# controller11_2.net
KiCad netlist of a schematic drawn in EAGLE
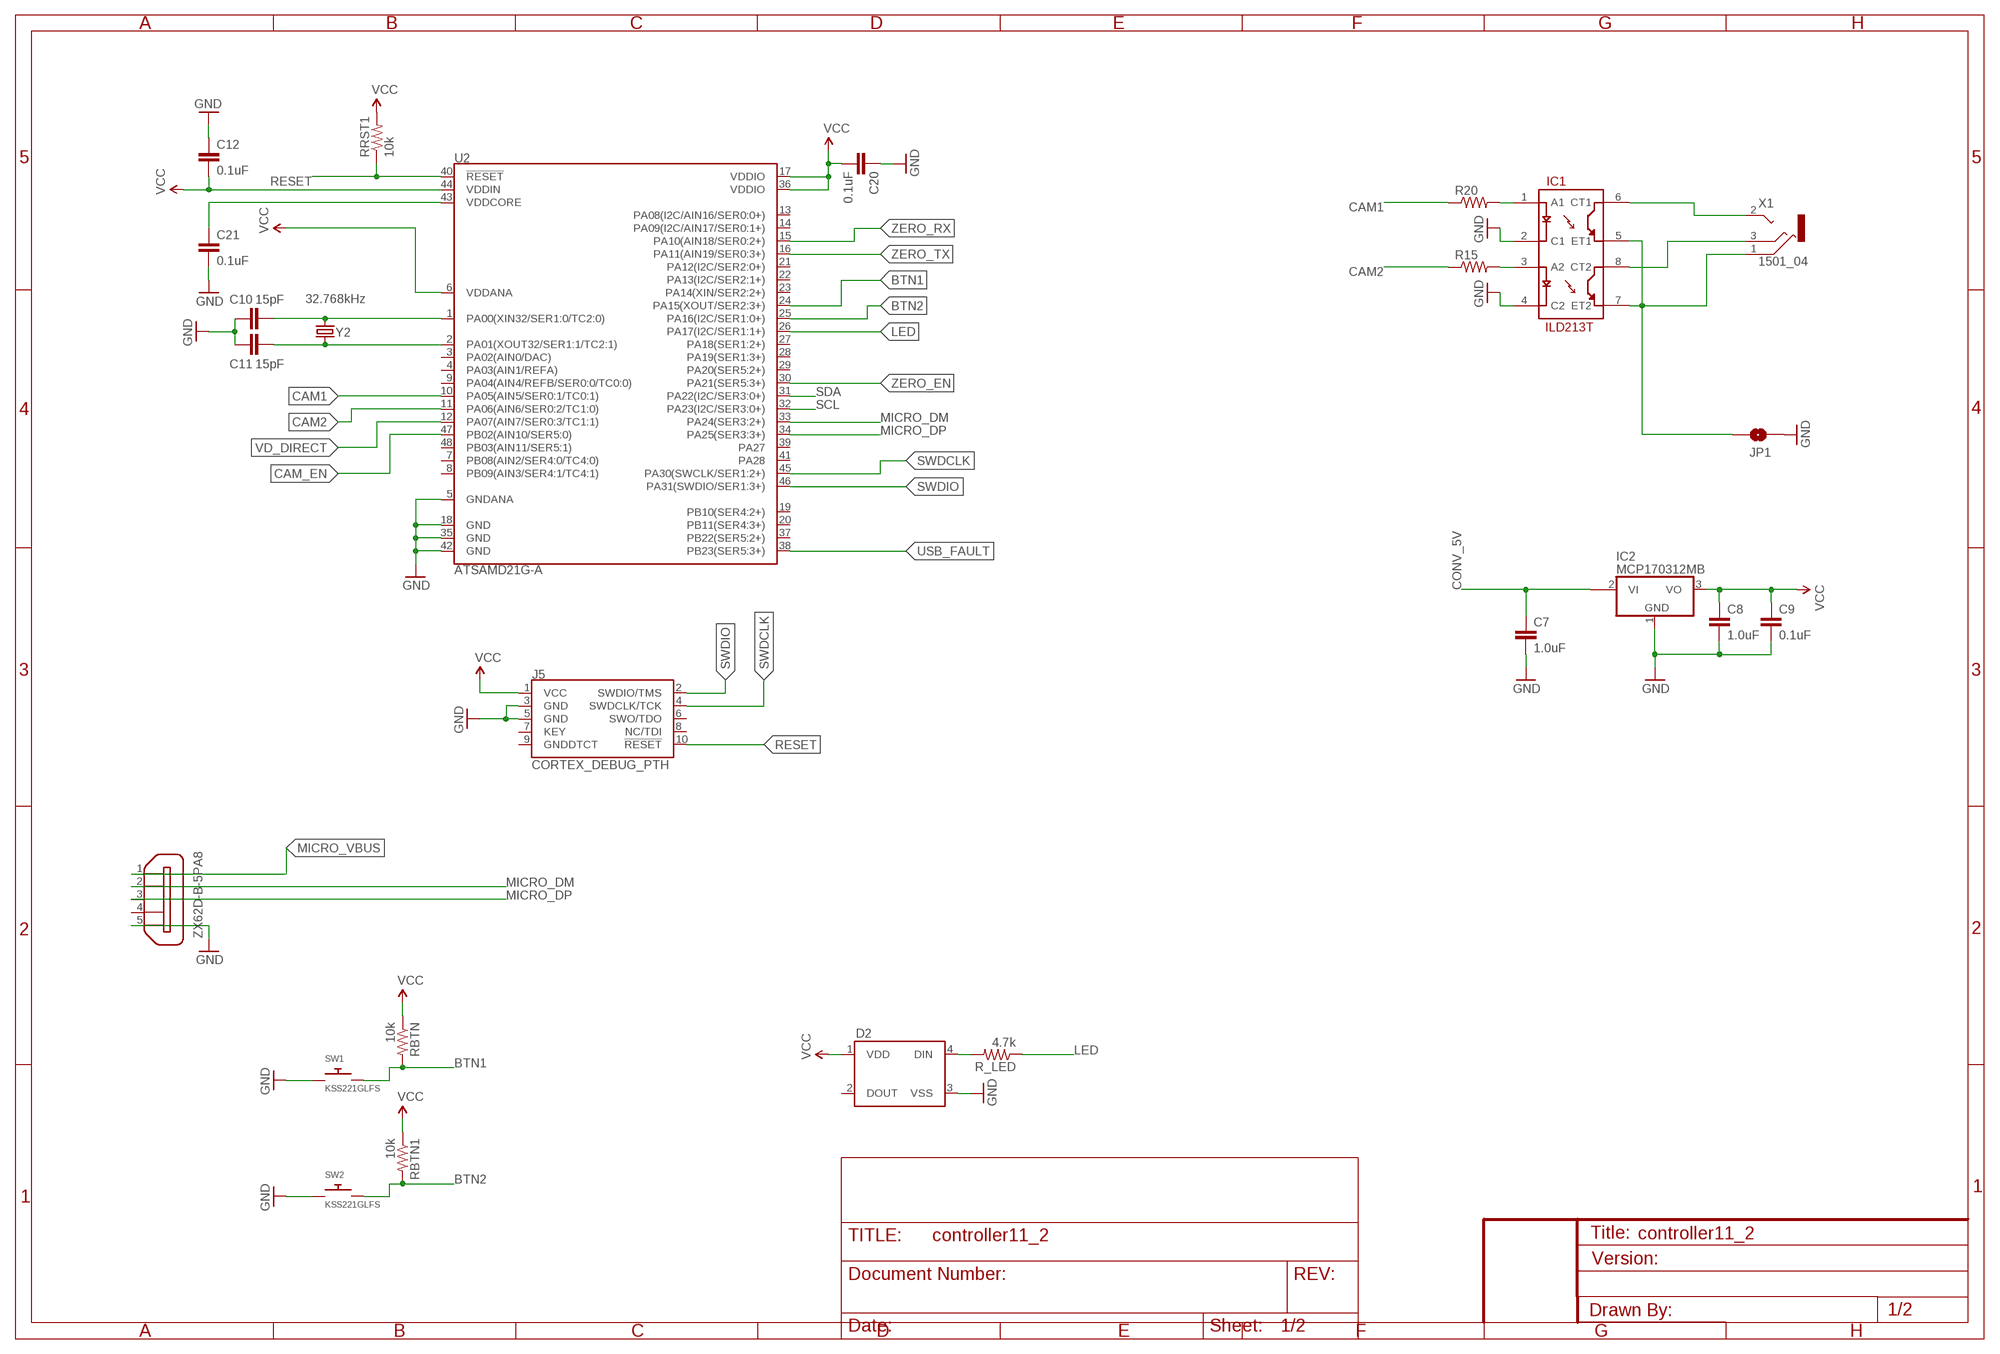
[diagram p0: schematic, sheet 1]
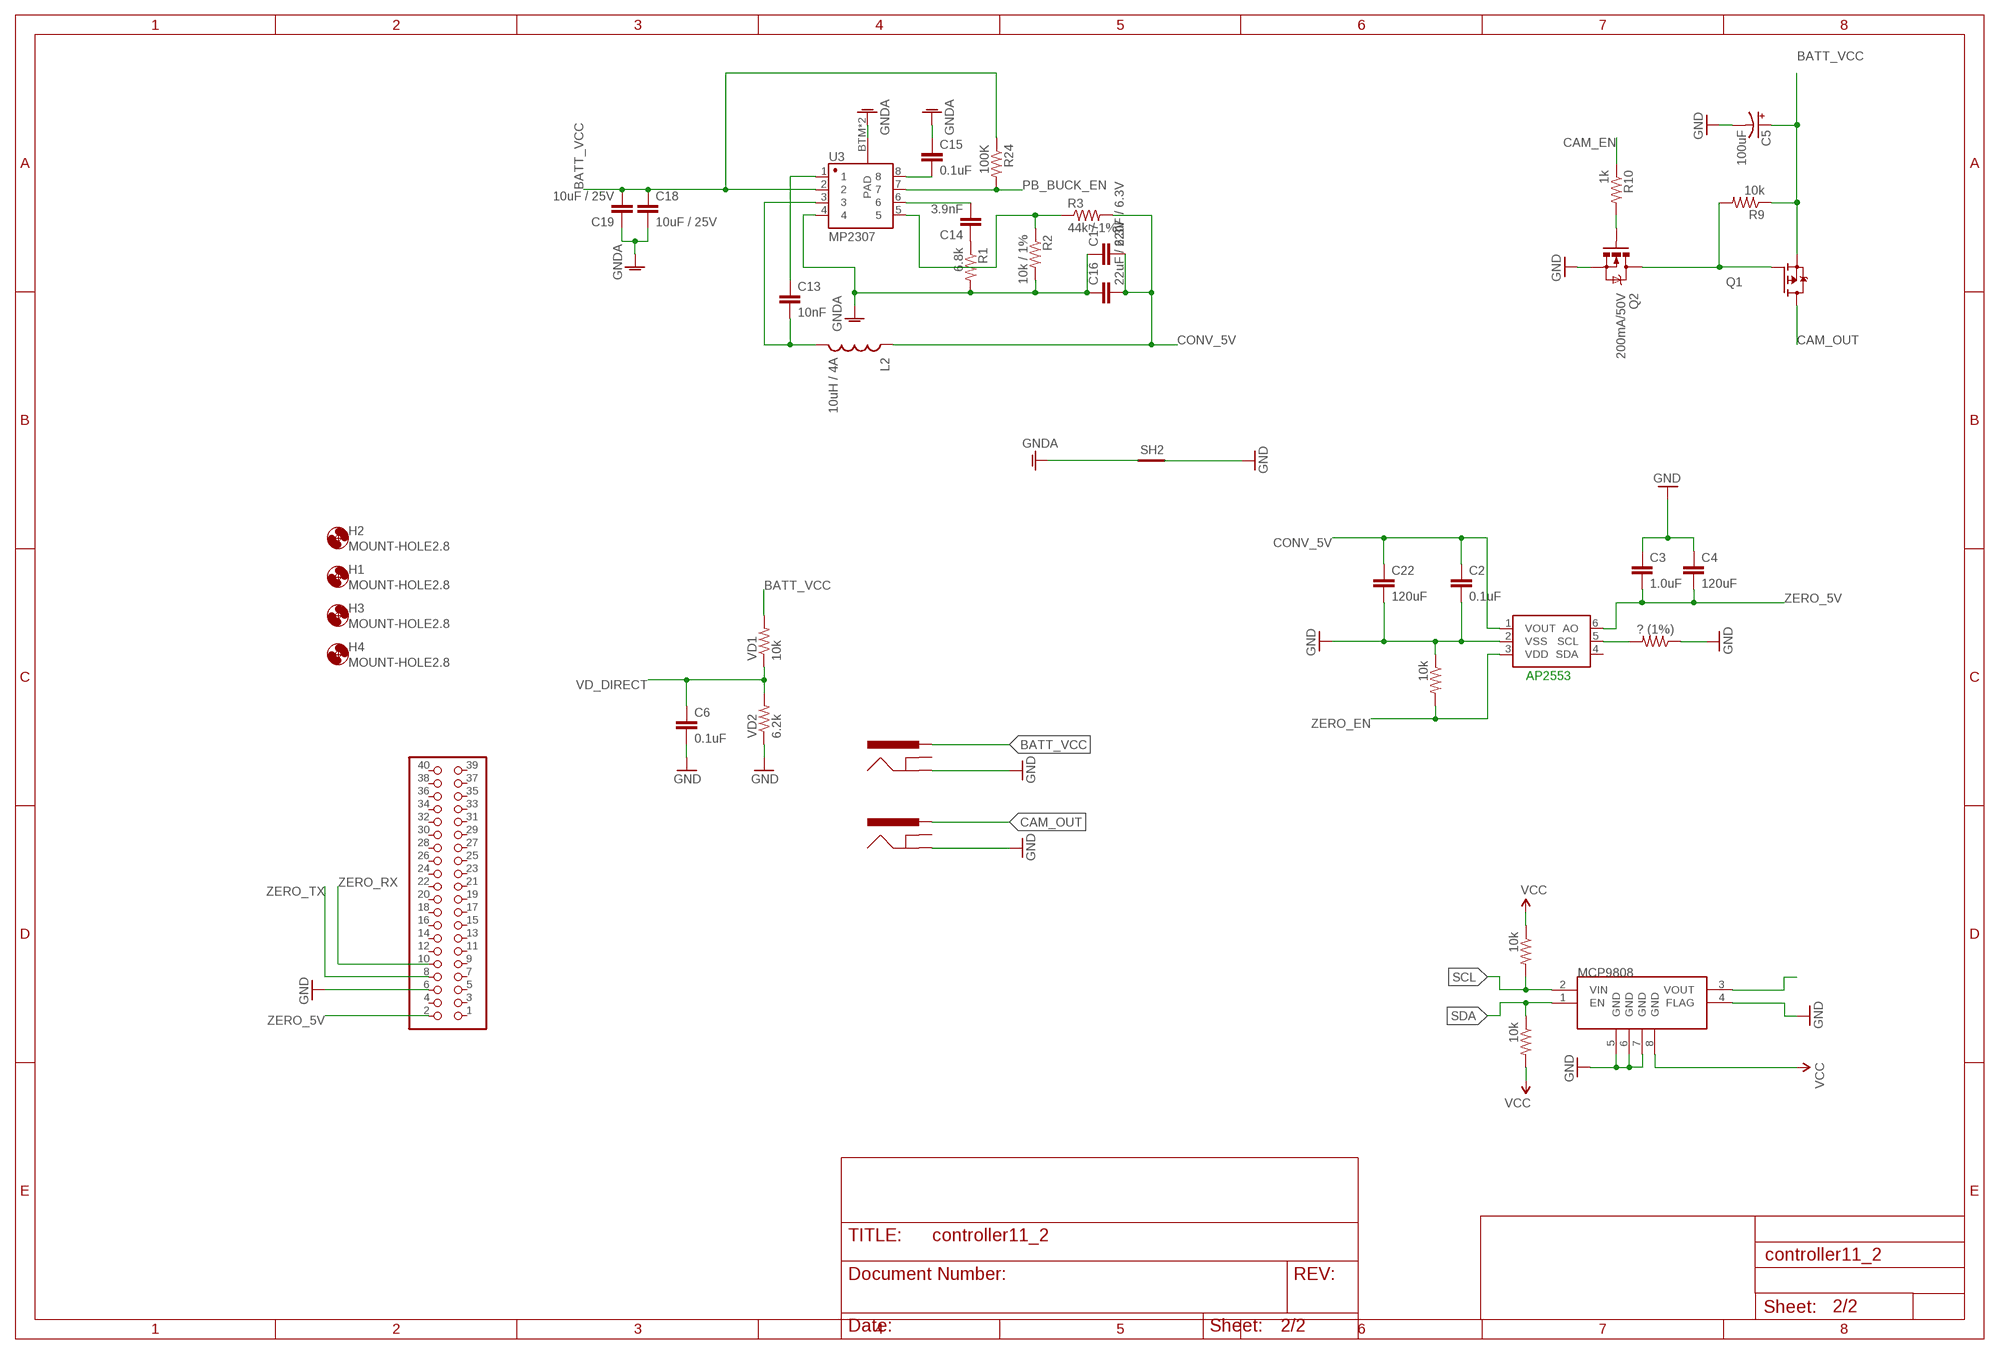
[diagram p1: schematic, sheet 2]

(export (version "E")
  (design (tool "Eeschema 10.0.6"))
  (components
    (comp (ref "C7")
      (value "1.0uF")
      (footprint "eagle-import:0805")
      (libsource (lib "eagle-import") (part "1.0UF-0805-25V-10%"))
    )
    (comp (ref "C8")
      (value "1.0uF")
      (footprint "eagle-import:1206")
      (libsource (lib "eagle-import") (part "1.0UF-1206-50V-10%"))
    )
    (comp (ref "C9")
      (value "0.1uF")
      (footprint "eagle-import:0805")
      (libsource (lib "eagle-import") (part "1.0UF-0805-25V-10%"))
    )
    (comp (ref "C10")
      (value "15pF")
      (footprint "eagle-import:0805")
      (libsource (lib "eagle-import") (part "SparkFun-Passives_CAP0805"))
    )
    (comp (ref "C11")
      (value "15pF")
      (footprint "eagle-import:0805")
      (libsource (lib "eagle-import") (part "SparkFun-Passives_CAP0805"))
    )
    (comp (ref "C12")
      (value "0.1uF")
      (footprint "eagle-import:0805")
      (libsource (lib "eagle-import") (part "1.0UF-0805-25V-10%"))
    )
    (comp (ref "C20")
      (value "0.1uF")
      (footprint "eagle-import:0805")
      (libsource (lib "eagle-import") (part "1.0UF-0805-25V-10%"))
    )
    (comp (ref "C21")
      (value "0.1uF")
      (footprint "eagle-import:0805")
      (libsource (lib "eagle-import") (part "1.0UF-0805-25V-10%"))
    )
    (comp (ref "D2")
      (value "WS2812B")
      (footprint "eagle-import:WS2812B")
      (libsource (lib "eagle-import") (part "WS2812B"))
    )
    (comp (ref "IC1")
      (value "ILD213T")
      (footprint "eagle-import:SO08")
      (libsource (lib "eagle-import") (part "ILD213T"))
    )
    (comp (ref "IC2")
      (value "MCP170312MB")
      (footprint "eagle-import:SOT89")
      (libsource (lib "eagle-import") (part "MCP1703MB12"))
    )
    (comp (ref "J5")
      (value "CORTEX_DEBUG_PTH")
      (footprint "eagle-import:2X5-PTH-1.27MM")
      (libsource (lib "eagle-import") (part "CORTEX_DEBUG_PTH"))
    )
    (comp (ref "JP1")
      (value "JUMPER-PAD-2-NOYES_SILK")
      (footprint "eagle-import:PAD-JUMPER-2-NO_YES_SILK")
      (libsource (lib "eagle-import") (part "JUMPER-PAD-2-NOYES_SILK"))
    )
    (comp (ref "R15")
      (value "RESISTOR0805-RES")
      (footprint "eagle-import:0805")
      (libsource (lib "eagle-import") (part "RESISTOR0805-RES"))
    )
    (comp (ref "R20")
      (value "RESISTOR0805-RES")
      (footprint "eagle-import:0805")
      (libsource (lib "eagle-import") (part "RESISTOR0805-RES"))
    )
    (comp (ref "RBTN")
      (value "10k")
      (footprint "eagle-import:0805")
      (libsource (lib "eagle-import") (part "RESISTOR0805-RES"))
    )
    (comp (ref "RBTN1")
      (value "10k")
      (footprint "eagle-import:0805")
      (libsource (lib "eagle-import") (part "RESISTOR0805-RES"))
    )
    (comp (ref "RRST1")
      (value "10k")
      (footprint "eagle-import:0805")
      (libsource (lib "eagle-import") (part "RESISTOR0805-RES"))
    )
    (comp (ref "R_LED")
      (value "4.7k")
      (footprint "eagle-import:0805")
      (libsource (lib "eagle-import") (part "SparkFun-Resistors_RESISTOR0805-RES"))
    )
    (comp (ref "SW1")
      (value "KSS221GLFS")
      (footprint "eagle-import:BTN_CK_KSS")
      (libsource (lib "eagle-import") (part "SWITCH_PUSHBUTTONC&K_KSS"))
    )
    (comp (ref "SW2")
      (value "KSS221GLFS")
      (footprint "eagle-import:BTN_CK_KSS")
      (libsource (lib "eagle-import") (part "SWITCH_PUSHBUTTONC&K_KSS"))
    )
    (comp (ref "U2")
      (value "ATSAMD21G-A")
      (footprint "eagle-import:TQFP-48")
      (libsource (lib "eagle-import") (part "ATSAMD21G-A"))
    )
    (comp (ref "X1")
      (value "1501_04")
      (footprint "eagle-import:1501_05")
      (libsource (lib "eagle-import") (part "1501_04"))
    )
    (comp (ref "X2")
      (value "ZX62D-B-5PA8")
      (footprint "eagle-import:ZX62D-B-5PA8")
      (fields (field (name "MF") "Hirose"))
      (libsource (lib "eagle-import") (part "ZX62D-B-5PA8"))
    )
    (comp (ref "Y2")
      (value "32.768kHz")
      (footprint "eagle-import:CRYSTAL-SMD-3.2X1.5MM")
      (libsource (lib "eagle-import") (part "CRYSTAL3.2X1.5MM"))
    )
    (comp (ref "AP2553")
      (value "MCP4725")
      (footprint "eagle-import:SOT23-6")
      (libsource (lib "eagle-import") (part "MCP4725SOT-23"))
    )
    (comp (ref "C2")
      (value "0.1uF")
      (footprint "eagle-import:0805")
      (libsource (lib "eagle-import") (part "1.0UF-0805-25V-10%"))
    )
    (comp (ref "C3")
      (value "1.0uF")
      (footprint "eagle-import:0805")
      (libsource (lib "eagle-import") (part "1.0UF-0805-25V-10%"))
    )
    (comp (ref "C4")
      (value "120uF")
      (footprint "eagle-import:1206")
      (libsource (lib "eagle-import") (part "1.0UF-1206-50V-10%"))
    )
    (comp (ref "C5")
      (value "100uF")
      (footprint "eagle-import:PANASONIC_D")
      (libsource (lib "eagle-import") (part "100UF-POLAR-25V-20%(ELEC)"))
    )
    (comp (ref "C6")
      (value "0.1uF")
      (footprint "eagle-import:1206")
      (libsource (lib "eagle-import") (part "CAP1206"))
    )
    (comp (ref "C13")
      (value "10nF")
      (footprint "eagle-import:1206")
      (libsource (lib "eagle-import") (part "CAP1206"))
    )
    (comp (ref "C14")
      (value "3.9nF")
      (footprint "eagle-import:1206")
      (libsource (lib "eagle-import") (part "CAP1206"))
    )
    (comp (ref "C15")
      (value "0.1uF")
      (footprint "eagle-import:1206")
      (libsource (lib "eagle-import") (part "CAP1206"))
    )
    (comp (ref "C16")
      (value "22uF / 6.3V")
      (footprint "eagle-import:1210")
      (libsource (lib "eagle-import") (part "CAP1210"))
    )
    (comp (ref "C17")
      (value "22uF / 6.3V")
      (footprint "eagle-import:1210")
      (libsource (lib "eagle-import") (part "CAP1210"))
    )
    (comp (ref "C18")
      (value "10uF / 25V")
      (footprint "eagle-import:1210")
      (libsource (lib "eagle-import") (part "CAP1210"))
    )
    (comp (ref "C19")
      (value "10uF / 25V")
      (footprint "eagle-import:1210")
      (libsource (lib "eagle-import") (part "CAP1210"))
    )
    (comp (ref "C22")
      (value "120uF")
      (footprint "eagle-import:1206")
      (libsource (lib "eagle-import") (part "1.0UF-1206-50V-10%"))
    )
    (comp (ref "H1")
      (value "MOUNT-HOLE2.8")
      (footprint "eagle-import:2,8")
      (libsource (lib "eagle-import") (part "MOUNT-HOLE2.8"))
    )
    (comp (ref "H2")
      (value "MOUNT-HOLE2.8")
      (footprint "eagle-import:2,8")
      (libsource (lib "eagle-import") (part "MOUNT-HOLE2.8"))
    )
    (comp (ref "H3")
      (value "MOUNT-HOLE2.8")
      (footprint "eagle-import:2,8")
      (libsource (lib "eagle-import") (part "MOUNT-HOLE2.8"))
    )
    (comp (ref "H4")
      (value "MOUNT-HOLE2.8")
      (footprint "eagle-import:2,8")
      (libsource (lib "eagle-import") (part "MOUNT-HOLE2.8"))
    )
    (comp (ref "J1")
      (value "POWER_JACKPTH_BREAD")
      (footprint "eagle-import:POWER_JACK_PTH_BREAD")
      (libsource (lib "eagle-import") (part "POWER_JACKPTH_BREAD"))
    )
    (comp (ref "J2")
      (value "POWER_JACKPTH_BREAD")
      (footprint "eagle-import:POWER_JACK_PTH_BREAD")
      (libsource (lib "eagle-import") (part "POWER_JACKPTH_BREAD"))
    )
    (comp (ref "JP2")
      (value "PINHD-2X20")
      (footprint "eagle-import:2X20")
      (libsource (lib "eagle-import") (part "PINHD-2X20"))
    )
    (comp (ref "L2")
      (value "10uH / 4A")
      (footprint "eagle-import:SRU1038")
      (libsource (lib "eagle-import") (part "INDUCTORSRU1038"))
    )
    (comp (ref "MCP9808")
      (value "V_REG_MIC5216")
      (footprint "eagle-import:MSOP8")
      (libsource (lib "eagle-import") (part "V_REG_MIC5216"))
    )
    (comp (ref "Q1")
      (value "FDD4141TO252")
      (footprint "eagle-import:TO252")
      (libsource (lib "eagle-import") (part "FDD4141TO252"))
    )
    (comp (ref "Q2")
      (value "200mA/50V")
      (footprint "eagle-import:SOT23-3")
      (libsource (lib "eagle-import") (part "MOSFET-NCHANNELBSS138"))
    )
    (comp (ref "R1")
      (value "6.8k")
      (footprint "eagle-import:1206")
      (libsource (lib "eagle-import") (part "SparkFun-Resistors_RESISTOR1206"))
    )
    (comp (ref "R2")
      (value "10k / 1%")
      (footprint "eagle-import:1206")
      (libsource (lib "eagle-import") (part "SparkFun-Resistors_RESISTOR1206"))
    )
    (comp (ref "R3")
      (value "44k / 1%")
      (footprint "eagle-import:1206")
      (libsource (lib "eagle-import") (part "SparkFun-Resistors_RESISTOR1206"))
    )
    (comp (ref "R9")
      (value "10k")
      (footprint "eagle-import:0805")
      (libsource (lib "eagle-import") (part "SparkFun-Resistors_RESISTOR0805-RES"))
    )
    (comp (ref "R10")
      (value "1k")
      (footprint "eagle-import:0805")
      (libsource (lib "eagle-import") (part "SparkFun-Resistors_RESISTOR0805-RES"))
    )
    (comp (ref "R24")
      (value "100K")
      (footprint "eagle-import:1206")
      (libsource (lib "eagle-import") (part "SparkFun-Resistors_RESISTOR1206"))
    )
    (comp (ref "R_I2C_1")
      (value "10k")
      (footprint "eagle-import:0805")
      (libsource (lib "eagle-import") (part "RESISTOR0805-RES"))
    )
    (comp (ref "R_I2C_2")
      (value "10k")
      (footprint "eagle-import:0805")
      (libsource (lib "eagle-import") (part "RESISTOR0805-RES"))
    )
    (comp (ref "R_MOSFET_USB1")
      (value "? (1%)")
      (footprint "eagle-import:0805")
      (libsource (lib "eagle-import") (part "RESISTOR0805-RES"))
    )
    (comp (ref "R_MOSFET_USB3")
      (value "10k")
      (footprint "eagle-import:0805")
      (libsource (lib "eagle-import") (part "RESISTOR0805-RES"))
    )
    (comp (ref "SH2")
      (value "SHORT-HT5")
      (footprint "eagle-import:SHORT_TOP-50")
      (libsource (lib "eagle-import") (part "SHORT-HT5"))
    )
    (comp (ref "U3")
      (value "MP2307")
      (footprint "eagle-import:SO08")
      (libsource (lib "eagle-import") (part "GENERIC-SOIC8MSGEQ7N-FILTER"))
    )
    (comp (ref "VD1")
      (value "10k")
      (footprint "eagle-import:1206")
      (libsource (lib "eagle-import") (part "RESISTOR1206"))
    )
    (comp (ref "VD2")
      (value "6.2k")
      (footprint "eagle-import:1206")
      (libsource (lib "eagle-import") (part "RESISTOR1206"))
    )
  )
  (nets
    (net (code "1") (name "BATT_VCC") (class "Default")
      (node (ref "C18") (pin "1") (pinfunction "1_1") (pintype "passive"))
      (node (ref "C19") (pin "2") (pinfunction "2_2") (pintype "passive"))
      (node (ref "C5") (pin "+") (pinfunction "+_+") (pintype "passive"))
      (node (ref "J1") (pin "PWR") (pinfunction "PWR_PWR") (pintype "bidirectional"))
      (node (ref "Q1") (pin "2") (pinfunction "S_2") (pintype "passive"))
      (node (ref "R24") (pin "1") (pinfunction "1_1") (pintype "passive"))
      (node (ref "R9") (pin "1") (pinfunction "1_1") (pintype "passive"))
      (node (ref "U3") (pin "2") (pinfunction "2_2") (pintype "bidirectional"))
      (node (ref "VD1") (pin "2") (pinfunction "2_2") (pintype "passive"))
    )
    (net (code "2") (name "BTN1") (class "Default")
      (node (ref "RBTN") (pin "2") (pinfunction "2_2") (pintype "passive"))
      (node (ref "SW1") (pin "P$2") (pinfunction "P$2_P$2") (pintype "passive"))
      (node (ref "U2") (pin "24") (pinfunction "PA15(XOUT/SER2:3+)_24") (pintype "bidirectional"))
    )
    (net (code "3") (name "BTN2") (class "Default")
      (node (ref "RBTN1") (pin "2") (pinfunction "2_2") (pintype "passive"))
      (node (ref "SW2") (pin "P$2") (pinfunction "P$2_P$2") (pintype "passive"))
      (node (ref "U2") (pin "25") (pinfunction "PA16(I2C/SER1:0+)_25") (pintype "bidirectional"))
    )
    (net (code "4") (name "CAM1") (class "Default")
      (node (ref "R20") (pin "1") (pinfunction "1_1") (pintype "passive"))
      (node (ref "U2") (pin "10") (pinfunction "PA05(AIN5/SER0:1/TC0:1)_10") (pintype "bidirectional"))
    )
    (net (code "5") (name "CAM2") (class "Default")
      (node (ref "R15") (pin "1") (pinfunction "1_1") (pintype "passive"))
      (node (ref "U2") (pin "11") (pinfunction "PA06(AIN6/SER0:2/TC1:0)_11") (pintype "bidirectional"))
    )
    (net (code "6") (name "CAM_EN") (class "Default")
      (node (ref "R10") (pin "1") (pinfunction "1_1") (pintype "passive"))
      (node (ref "U2") (pin "47") (pinfunction "PB02(AIN10/SER5:0)_47") (pintype "bidirectional"))
    )
    (net (code "7") (name "CAM_OUT") (class "Default")
      (node (ref "J2") (pin "PWR") (pinfunction "PWR_PWR") (pintype "bidirectional"))
      (node (ref "Q1") (pin "3") (pinfunction "D_3") (pintype "passive"))
    )
    (net (code "8") (name "CONV_5V") (class "Default")
      (node (ref "AP2553") (pin "1") (pinfunction "VOUT_1") (pintype "bidirectional"))
      (node (ref "C16") (pin "2") (pinfunction "2_2") (pintype "passive"))
      (node (ref "C17") (pin "2") (pinfunction "2_2") (pintype "passive"))
      (node (ref "C2") (pin "1") (pinfunction "1_1") (pintype "passive"))
      (node (ref "C22") (pin "1") (pinfunction "1_1") (pintype "passive"))
      (node (ref "C7") (pin "1") (pinfunction "1_1") (pintype "passive"))
      (node (ref "IC2") (pin "2@1") (pinfunction "VI1_2@1") (pintype "input"))
      (node (ref "L2") (pin "1") (pinfunction "1_1") (pintype "passive"))
      (node (ref "R3") (pin "2") (pinfunction "2_2") (pintype "passive"))
    )
    (net (code "9") (name "GND") (class "Default")
      (node (ref "AP2553") (pin "2") (pinfunction "VSS_2") (pintype "bidirectional"))
      (node (ref "C10") (pin "1") (pinfunction "1_1") (pintype "passive"))
      (node (ref "C11") (pin "1") (pinfunction "1_1") (pintype "passive"))
      (node (ref "C12") (pin "1") (pinfunction "1_1") (pintype "passive"))
      (node (ref "C2") (pin "2") (pinfunction "2_2") (pintype "passive"))
      (node (ref "C20") (pin "1") (pinfunction "1_1") (pintype "passive"))
      (node (ref "C21") (pin "2") (pinfunction "2_2") (pintype "passive"))
      (node (ref "C22") (pin "2") (pinfunction "2_2") (pintype "passive"))
      (node (ref "C3") (pin "1") (pinfunction "1_1") (pintype "passive"))
      (node (ref "C4") (pin "1") (pinfunction "1_1") (pintype "passive"))
      (node (ref "C5") (pin "-") (pinfunction "-_-") (pintype "passive"))
      (node (ref "C6") (pin "2") (pinfunction "2_2") (pintype "passive"))
      (node (ref "C7") (pin "2") (pinfunction "2_2") (pintype "passive"))
      (node (ref "C8") (pin "2") (pinfunction "2_2") (pintype "passive"))
      (node (ref "C9") (pin "2") (pinfunction "2_2") (pintype "passive"))
      (node (ref "D2") (pin "3") (pinfunction "VSS_3") (pintype "power_in"))
      (node (ref "IC1") (pin "2") (pinfunction "C1_2") (pintype "bidirectional"))
      (node (ref "IC1") (pin "4") (pinfunction "C2_4") (pintype "bidirectional"))
      (node (ref "IC2") (pin "1") (pinfunction "GND_1") (pintype "passive"))
      (node (ref "J1") (pin "GND") (pinfunction "GND_GND") (pintype "bidirectional"))
      (node (ref "J2") (pin "GND") (pinfunction "GND_GND") (pintype "bidirectional"))
      (node (ref "J5") (pin "3") (pinfunction "GND_3") (pintype "bidirectional"))
      (node (ref "J5") (pin "5") (pinfunction "GND_5") (pintype "bidirectional"))
      (node (ref "JP1") (pin "1") (pinfunction "1_1") (pintype "passive"))
      (node (ref "JP2") (pin "6") (pinfunction "6_6") (pintype "passive"))
      (node (ref "MCP9808") (pin "4") (pinfunction "FLAG_4") (pintype "bidirectional"))
      (node (ref "MCP9808") (pin "5") (pinfunction "GND_5") (pintype "bidirectional"))
      (node (ref "MCP9808") (pin "6") (pinfunction "GND_6") (pintype "bidirectional"))
      (node (ref "MCP9808") (pin "7") (pinfunction "GND_7") (pintype "bidirectional"))
      (node (ref "Q2") (pin "2") (pinfunction "S_2") (pintype "passive"))
      (node (ref "R_MOSFET_USB1") (pin "1") (pinfunction "1_1") (pintype "passive"))
      (node (ref "R_MOSFET_USB3") (pin "1") (pinfunction "1_1") (pintype "passive"))
      (node (ref "SH2") (pin "2") (pinfunction "P$2_2") (pintype "bidirectional"))
      (node (ref "SW1") (pin "P$1") (pinfunction "P$1_P$1") (pintype "passive"))
      (node (ref "SW2") (pin "P$1") (pinfunction "P$1_P$1") (pintype "passive"))
      (node (ref "U2") (pin "18") (pinfunction "GND_18") (pintype "bidirectional"))
      (node (ref "U2") (pin "35") (pinfunction "GND_35") (pintype "bidirectional"))
      (node (ref "U2") (pin "42") (pinfunction "GND_42") (pintype "bidirectional"))
      (node (ref "U2") (pin "5") (pinfunction "GNDANA_5") (pintype "bidirectional"))
      (node (ref "VD2") (pin "1") (pinfunction "1_1") (pintype "passive"))
      (node (ref "X2") (pin "5") (pinfunction "5_5") (pintype "passive"))
    )
    (net (code "10") (name "GNDA") (class "Default")
      (node (ref "C15") (pin "1") (pinfunction "1_1") (pintype "passive"))
      (node (ref "C16") (pin "1") (pinfunction "1_1") (pintype "passive"))
      (node (ref "C17") (pin "1") (pinfunction "1_1") (pintype "passive"))
      (node (ref "C18") (pin "2") (pinfunction "2_2") (pintype "passive"))
      (node (ref "C19") (pin "1") (pinfunction "1_1") (pintype "passive"))
      (node (ref "R1") (pin "2") (pinfunction "2_2") (pintype "passive"))
      (node (ref "R2") (pin "2") (pinfunction "2_2") (pintype "passive"))
      (node (ref "SH2") (pin "1") (pinfunction "P$1_1") (pintype "bidirectional"))
      (node (ref "U3") (pin "4") (pinfunction "4_4") (pintype "bidirectional"))
      (node (ref "U3") (pin "BTM") (pinfunction "PAD_BTM") (pintype "bidirectional"))
      (node (ref "U3") (pin "P$1") (pinfunction "PAD_P$1") (pintype "bidirectional"))
    )
    (net (code "11") (name "LED") (class "Default")
      (node (ref "R_LED") (pin "1") (pinfunction "1_1") (pintype "passive"))
      (node (ref "U2") (pin "26") (pinfunction "PA17(I2C/SER1:1+)_26") (pintype "bidirectional"))
    )
    (net (code "12") (name "MICRO_DM") (class "Default")
      (node (ref "U2") (pin "33") (pinfunction "PA24(SER3:2+)_33") (pintype "bidirectional"))
      (node (ref "X2") (pin "2") (pinfunction "2_2") (pintype "passive"))
    )
    (net (code "13") (name "MICRO_DP") (class "Default")
      (node (ref "U2") (pin "34") (pinfunction "PA25(SER3:3+)_34") (pintype "bidirectional"))
      (node (ref "X2") (pin "3") (pinfunction "3_3") (pintype "passive"))
    )
    (net (code "14") (name "MICRO_VBUS") (class "Default")
      (node (ref "X2") (pin "1") (pinfunction "1_1") (pintype "passive"))
    )
    (net (code "15") (name "Net-(AP2553-SCL)") (class "Default")
      (node (ref "AP2553") (pin "5") (pinfunction "SCL_5") (pintype "bidirectional"))
      (node (ref "R_MOSFET_USB1") (pin "2") (pinfunction "2_2") (pintype "passive"))
    )
    (net (code "16") (name "Net-(C13-Pad1)") (class "Default")
      (node (ref "C13") (pin "1") (pinfunction "1_1") (pintype "passive"))
      (node (ref "U3") (pin "1") (pinfunction "1_1") (pintype "bidirectional"))
    )
    (net (code "17") (name "Net-(C13-Pad2)") (class "Default")
      (node (ref "C13") (pin "2") (pinfunction "2_2") (pintype "passive"))
      (node (ref "L2") (pin "2") (pinfunction "2_2") (pintype "passive"))
      (node (ref "U3") (pin "3") (pinfunction "3_3") (pintype "bidirectional"))
    )
    (net (code "18") (name "Net-(C14-Pad1)") (class "Default")
      (node (ref "C14") (pin "1") (pinfunction "1_1") (pintype "passive"))
      (node (ref "R1") (pin "1") (pinfunction "1_1") (pintype "passive"))
    )
    (net (code "19") (name "Net-(C14-Pad2)") (class "Default")
      (node (ref "C14") (pin "2") (pinfunction "2_2") (pintype "passive"))
      (node (ref "U3") (pin "6") (pinfunction "6_6") (pintype "bidirectional"))
    )
    (net (code "20") (name "Net-(C15-Pad2)") (class "Default")
      (node (ref "C15") (pin "2") (pinfunction "2_2") (pintype "passive"))
      (node (ref "U3") (pin "8") (pinfunction "8_8") (pintype "bidirectional"))
    )
    (net (code "21") (name "Net-(D2-DIN)") (class "Default")
      (node (ref "D2") (pin "4") (pinfunction "DIN_4") (pintype "input"))
      (node (ref "R_LED") (pin "2") (pinfunction "2_2") (pintype "passive"))
    )
    (net (code "22") (name "Net-(IC1-A1)") (class "Default")
      (node (ref "IC1") (pin "1") (pinfunction "A1_1") (pintype "bidirectional"))
      (node (ref "R20") (pin "2") (pinfunction "2_2") (pintype "passive"))
    )
    (net (code "23") (name "Net-(IC1-A2)") (class "Default")
      (node (ref "IC1") (pin "3") (pinfunction "A2_3") (pintype "bidirectional"))
      (node (ref "R15") (pin "2") (pinfunction "2_2") (pintype "passive"))
    )
    (net (code "24") (name "Net-(IC1-CT1)") (class "Default")
      (node (ref "IC1") (pin "6") (pinfunction "CT1_6") (pintype "bidirectional"))
      (node (ref "X1") (pin "2") (pinfunction "2_2") (pintype "passive"))
    )
    (net (code "25") (name "Net-(IC1-CT2)") (class "Default")
      (node (ref "IC1") (pin "8") (pinfunction "CT2_8") (pintype "bidirectional"))
      (node (ref "X1") (pin "3") (pinfunction "3_3") (pintype "passive"))
    )
    (net (code "26") (name "Net-(IC1-ET1)") (class "Default")
      (node (ref "IC1") (pin "5") (pinfunction "ET1_5") (pintype "bidirectional"))
      (node (ref "IC1") (pin "7") (pinfunction "ET2_7") (pintype "bidirectional"))
      (node (ref "JP1") (pin "2") (pinfunction "2_2") (pintype "passive"))
      (node (ref "X1") (pin "1") (pinfunction "1_1") (pintype "passive"))
    )
    (net (code "27") (name "Net-(Q1-G)") (class "Default")
      (node (ref "Q1") (pin "1") (pinfunction "G_1") (pintype "passive"))
      (node (ref "Q2") (pin "3") (pinfunction "D_3") (pintype "passive"))
      (node (ref "R9") (pin "2") (pinfunction "2_2") (pintype "passive"))
    )
    (net (code "28") (name "Net-(Q2-G)") (class "Default")
      (node (ref "Q2") (pin "1") (pinfunction "G_1") (pintype "passive"))
      (node (ref "R10") (pin "2") (pinfunction "2_2") (pintype "passive"))
    )
    (net (code "29") (name "Net-(R2-Pad1)") (class "Default")
      (node (ref "R2") (pin "1") (pinfunction "1_1") (pintype "passive"))
      (node (ref "R3") (pin "1") (pinfunction "1_1") (pintype "passive"))
      (node (ref "U3") (pin "5") (pinfunction "5_5") (pintype "bidirectional"))
    )
    (net (code "30") (name "Net-(U2-PA00(XIN32{slash}SER1:0{slash}TC2:0))") (class "Default")
      (node (ref "C10") (pin "2") (pinfunction "2_2") (pintype "passive"))
      (node (ref "U2") (pin "1") (pinfunction "PA00(XIN32/SER1:0/TC2:0)_1") (pintype "bidirectional"))
      (node (ref "Y2") (pin "P$2") (pinfunction "2_P$2") (pintype "passive"))
    )
    (net (code "31") (name "Net-(U2-PA01(XOUT32{slash}SER1:1{slash}TC2:1))") (class "Default")
      (node (ref "C11") (pin "2") (pinfunction "2_2") (pintype "passive"))
      (node (ref "U2") (pin "2") (pinfunction "PA01(XOUT32/SER1:1/TC2:1)_2") (pintype "bidirectional"))
      (node (ref "Y2") (pin "P$1") (pinfunction "1_P$1") (pintype "passive"))
    )
    (net (code "32") (name "Net-(U2-VDDCORE)") (class "Default")
      (node (ref "C21") (pin "1") (pinfunction "1_1") (pintype "passive"))
      (node (ref "U2") (pin "43") (pinfunction "VDDCORE_43") (pintype "bidirectional"))
    )
    (net (code "33") (name "PB_BUCK_EN") (class "Default")
      (node (ref "R24") (pin "2") (pinfunction "2_2") (pintype "passive"))
      (node (ref "U3") (pin "7") (pinfunction "7_7") (pintype "bidirectional"))
    )
    (net (code "34") (name "RESET") (class "Default")
      (node (ref "J5") (pin "10") (pinfunction "~{RESET}_10") (pintype "bidirectional"))
      (node (ref "RRST1") (pin "1") (pinfunction "1_1") (pintype "passive"))
      (node (ref "U2") (pin "40") (pinfunction "~{RESET}_40") (pintype "bidirectional"))
    )
    (net (code "35") (name "SCL") (class "Default")
      (node (ref "MCP9808") (pin "2") (pinfunction "VIN_2") (pintype "bidirectional"))
      (node (ref "R_I2C_1") (pin "2") (pinfunction "2_2") (pintype "passive"))
      (node (ref "U2") (pin "32") (pinfunction "PA23(I2C/SER3:0+)_32") (pintype "bidirectional"))
    )
    (net (code "36") (name "SDA") (class "Default")
      (node (ref "MCP9808") (pin "1") (pinfunction "EN_1") (pintype "bidirectional"))
      (node (ref "R_I2C_2") (pin "1") (pinfunction "1_1") (pintype "passive"))
      (node (ref "U2") (pin "31") (pinfunction "PA22(I2C/SER3:0+)_31") (pintype "bidirectional"))
    )
    (net (code "37") (name "SWDCLK") (class "Default")
      (node (ref "J5") (pin "4") (pinfunction "SWDCLK/TCK_4") (pintype "bidirectional"))
      (node (ref "U2") (pin "45") (pinfunction "PA30(SWCLK/SER1:2+)_45") (pintype "bidirectional"))
    )
    (net (code "38") (name "SWDIO") (class "Default")
      (node (ref "J5") (pin "2") (pinfunction "SWDIO/TMS_2") (pintype "bidirectional"))
      (node (ref "U2") (pin "46") (pinfunction "PA31(SWDIO/SER1:3+)_46") (pintype "bidirectional"))
    )
    (net (code "39") (name "USB_FAULT") (class "Default")
      (node (ref "U2") (pin "38") (pinfunction "PB23(SER5:3+)_38") (pintype "bidirectional"))
    )
    (net (code "40") (name "VCC") (class "Default")
      (node (ref "C12") (pin "2") (pinfunction "2_2") (pintype "passive"))
      (node (ref "C20") (pin "2") (pinfunction "2_2") (pintype "passive"))
      (node (ref "C8") (pin "1") (pinfunction "1_1") (pintype "passive"))
      (node (ref "C9") (pin "1") (pinfunction "1_1") (pintype "passive"))
      (node (ref "D2") (pin "1") (pinfunction "VDD_1") (pintype "power_in"))
      (node (ref "IC2") (pin "3") (pinfunction "VO_3") (pintype "passive"))
      (node (ref "J5") (pin "1") (pinfunction "VCC_1") (pintype "bidirectional"))
      (node (ref "MCP9808") (pin "8") (pinfunction "GND_8") (pintype "bidirectional"))
      (node (ref "RBTN") (pin "1") (pinfunction "1_1") (pintype "passive"))
      (node (ref "RBTN1") (pin "1") (pinfunction "1_1") (pintype "passive"))
      (node (ref "RRST1") (pin "2") (pinfunction "2_2") (pintype "passive"))
      (node (ref "R_I2C_1") (pin "1") (pinfunction "1_1") (pintype "passive"))
      (node (ref "R_I2C_2") (pin "2") (pinfunction "2_2") (pintype "passive"))
      (node (ref "U2") (pin "17") (pinfunction "VDDIO_17") (pintype "bidirectional"))
      (node (ref "U2") (pin "36") (pinfunction "VDDIO_36") (pintype "bidirectional"))
      (node (ref "U2") (pin "44") (pinfunction "VDDIN_44") (pintype "bidirectional"))
      (node (ref "U2") (pin "6") (pinfunction "VDDANA_6") (pintype "bidirectional"))
    )
    (net (code "41") (name "VD_DIRECT") (class "Default")
      (node (ref "C6") (pin "1") (pinfunction "1_1") (pintype "passive"))
      (node (ref "U2") (pin "12") (pinfunction "PA07(AIN7/SER0:3/TC1:1)_12") (pintype "bidirectional"))
      (node (ref "VD1") (pin "1") (pinfunction "1_1") (pintype "passive"))
      (node (ref "VD2") (pin "2") (pinfunction "2_2") (pintype "passive"))
    )
    (net (code "42") (name "ZERO_5V") (class "Default")
      (node (ref "AP2553") (pin "6") (pinfunction "AO_6") (pintype "bidirectional"))
      (node (ref "C3") (pin "2") (pinfunction "2_2") (pintype "passive"))
      (node (ref "C4") (pin "2") (pinfunction "2_2") (pintype "passive"))
      (node (ref "JP2") (pin "2") (pinfunction "2_2") (pintype "passive"))
    )
    (net (code "43") (name "ZERO_EN") (class "Default")
      (node (ref "AP2553") (pin "3") (pinfunction "VDD_3") (pintype "bidirectional"))
      (node (ref "R_MOSFET_USB3") (pin "2") (pinfunction "2_2") (pintype "passive"))
      (node (ref "U2") (pin "30") (pinfunction "PA21(SER5:3+)_30") (pintype "bidirectional"))
    )
    (net (code "44") (name "ZERO_RX") (class "Default")
      (node (ref "JP2") (pin "10") (pinfunction "10_10") (pintype "passive"))
      (node (ref "U2") (pin "15") (pinfunction "PA10(AIN18/SER0:2+)_15") (pintype "bidirectional"))
    )
    (net (code "45") (name "ZERO_TX") (class "Default")
      (node (ref "JP2") (pin "8") (pinfunction "8_8") (pintype "passive"))
      (node (ref "U2") (pin "16") (pinfunction "PA11(AIN19/SER0:3+)_16") (pintype "bidirectional"))
    )
    (net (code "46") (name "unconnected-(AP2553-SDA-Pad4)") (class "Default")
      (node (ref "AP2553") (pin "4") (pinfunction "SDA_4") (pintype "bidirectional"))
    )
    (net (code "47") (name "unconnected-(D2-DOUT-Pad2)") (class "Default")
      (node (ref "D2") (pin "2") (pinfunction "DOUT_2") (pintype "output"))
    )
    (net (code "48") (name "unconnected-(IC2-VI-Pad2)") (class "Default")
      (node (ref "IC2") (pin "2") (pinfunction "VI_2") (pintype "input"))
    )
    (net (code "49") (name "unconnected-(J1-PadGNDBREAK)") (class "Default")
      (node (ref "J1") (pin "GNDBREAK") (pinfunction "GNDBREAK_GNDBREAK") (pintype "bidirectional"))
    )
    (net (code "50") (name "unconnected-(J2-PadGNDBREAK)") (class "Default")
      (node (ref "J2") (pin "GNDBREAK") (pinfunction "GNDBREAK_GNDBREAK") (pintype "bidirectional"))
    )
    (net (code "51") (name "unconnected-(J5-GNDDTCT-Pad9)") (class "Default")
      (node (ref "J5") (pin "9") (pinfunction "GNDDTCT_9") (pintype "bidirectional"))
    )
    (net (code "52") (name "unconnected-(J5-KEY-Pad7)") (class "Default")
      (node (ref "J5") (pin "7") (pinfunction "KEY_7") (pintype "bidirectional"))
    )
    (net (code "53") (name "unconnected-(J5-NC{slash}TDI-Pad8)") (class "Default")
      (node (ref "J5") (pin "8") (pinfunction "NC/TDI_8") (pintype "bidirectional"))
    )
    (net (code "54") (name "unconnected-(J5-SWO{slash}TDO-Pad6)") (class "Default")
      (node (ref "J5") (pin "6") (pinfunction "SWO/TDO_6") (pintype "bidirectional"))
    )
    (net (code "55") (name "unconnected-(JP2-Pad1)") (class "Default")
      (node (ref "JP2") (pin "1") (pinfunction "1_1") (pintype "passive"))
    )
    (net (code "56") (name "unconnected-(JP2-Pad3)") (class "Default")
      (node (ref "JP2") (pin "3") (pinfunction "3_3") (pintype "passive"))
    )
    (net (code "57") (name "unconnected-(JP2-Pad4)") (class "Default")
      (node (ref "JP2") (pin "4") (pinfunction "4_4") (pintype "passive"))
    )
    (net (code "58") (name "unconnected-(JP2-Pad5)") (class "Default")
      (node (ref "JP2") (pin "5") (pinfunction "5_5") (pintype "passive"))
    )
    (net (code "59") (name "unconnected-(JP2-Pad7)") (class "Default")
      (node (ref "JP2") (pin "7") (pinfunction "7_7") (pintype "passive"))
    )
    (net (code "60") (name "unconnected-(JP2-Pad9)") (class "Default")
      (node (ref "JP2") (pin "9") (pinfunction "9_9") (pintype "passive"))
    )
    (net (code "61") (name "unconnected-(JP2-Pad11)") (class "Default")
      (node (ref "JP2") (pin "11") (pinfunction "11_11") (pintype "passive"))
    )
    (net (code "62") (name "unconnected-(JP2-Pad12)") (class "Default")
      (node (ref "JP2") (pin "12") (pinfunction "12_12") (pintype "passive"))
    )
    (net (code "63") (name "unconnected-(JP2-Pad13)") (class "Default")
      (node (ref "JP2") (pin "13") (pinfunction "13_13") (pintype "passive"))
    )
    (net (code "64") (name "unconnected-(JP2-Pad14)") (class "Default")
      (node (ref "JP2") (pin "14") (pinfunction "14_14") (pintype "passive"))
    )
    (net (code "65") (name "unconnected-(JP2-Pad15)") (class "Default")
      (node (ref "JP2") (pin "15") (pinfunction "15_15") (pintype "passive"))
    )
    (net (code "66") (name "unconnected-(JP2-Pad16)") (class "Default")
      (node (ref "JP2") (pin "16") (pinfunction "16_16") (pintype "passive"))
    )
    (net (code "67") (name "unconnected-(JP2-Pad17)") (class "Default")
      (node (ref "JP2") (pin "17") (pinfunction "17_17") (pintype "passive"))
    )
    (net (code "68") (name "unconnected-(JP2-Pad18)") (class "Default")
      (node (ref "JP2") (pin "18") (pinfunction "18_18") (pintype "passive"))
    )
    (net (code "69") (name "unconnected-(JP2-Pad19)") (class "Default")
      (node (ref "JP2") (pin "19") (pinfunction "19_19") (pintype "passive"))
    )
    (net (code "70") (name "unconnected-(JP2-Pad20)") (class "Default")
      (node (ref "JP2") (pin "20") (pinfunction "20_20") (pintype "passive"))
    )
    (net (code "71") (name "unconnected-(JP2-Pad21)") (class "Default")
      (node (ref "JP2") (pin "21") (pinfunction "21_21") (pintype "passive"))
    )
    (net (code "72") (name "unconnected-(JP2-Pad22)") (class "Default")
      (node (ref "JP2") (pin "22") (pinfunction "22_22") (pintype "passive"))
    )
    (net (code "73") (name "unconnected-(JP2-Pad23)") (class "Default")
      (node (ref "JP2") (pin "23") (pinfunction "23_23") (pintype "passive"))
    )
    (net (code "74") (name "unconnected-(JP2-Pad24)") (class "Default")
      (node (ref "JP2") (pin "24") (pinfunction "24_24") (pintype "passive"))
    )
    (net (code "75") (name "unconnected-(JP2-Pad25)") (class "Default")
      (node (ref "JP2") (pin "25") (pinfunction "25_25") (pintype "passive"))
    )
    (net (code "76") (name "unconnected-(JP2-Pad26)") (class "Default")
      (node (ref "JP2") (pin "26") (pinfunction "26_26") (pintype "passive"))
    )
    (net (code "77") (name "unconnected-(JP2-Pad27)") (class "Default")
      (node (ref "JP2") (pin "27") (pinfunction "27_27") (pintype "passive"))
    )
    (net (code "78") (name "unconnected-(JP2-Pad28)") (class "Default")
      (node (ref "JP2") (pin "28") (pinfunction "28_28") (pintype "passive"))
    )
    (net (code "79") (name "unconnected-(JP2-Pad29)") (class "Default")
      (node (ref "JP2") (pin "29") (pinfunction "29_29") (pintype "passive"))
    )
    (net (code "80") (name "unconnected-(JP2-Pad30)") (class "Default")
      (node (ref "JP2") (pin "30") (pinfunction "30_30") (pintype "passive"))
    )
    (net (code "81") (name "unconnected-(JP2-Pad31)") (class "Default")
      (node (ref "JP2") (pin "31") (pinfunction "31_31") (pintype "passive"))
    )
    (net (code "82") (name "unconnected-(JP2-Pad32)") (class "Default")
      (node (ref "JP2") (pin "32") (pinfunction "32_32") (pintype "passive"))
    )
    (net (code "83") (name "unconnected-(JP2-Pad33)") (class "Default")
      (node (ref "JP2") (pin "33") (pinfunction "33_33") (pintype "passive"))
    )
    (net (code "84") (name "unconnected-(JP2-Pad34)") (class "Default")
      (node (ref "JP2") (pin "34") (pinfunction "34_34") (pintype "passive"))
    )
    (net (code "85") (name "unconnected-(JP2-Pad35)") (class "Default")
      (node (ref "JP2") (pin "35") (pinfunction "35_35") (pintype "passive"))
    )
    (net (code "86") (name "unconnected-(JP2-Pad36)") (class "Default")
      (node (ref "JP2") (pin "36") (pinfunction "36_36") (pintype "passive"))
    )
    (net (code "87") (name "unconnected-(JP2-Pad37)") (class "Default")
      (node (ref "JP2") (pin "37") (pinfunction "37_37") (pintype "passive"))
    )
    (net (code "88") (name "unconnected-(JP2-Pad38)") (class "Default")
      (node (ref "JP2") (pin "38") (pinfunction "38_38") (pintype "passive"))
    )
    (net (code "89") (name "unconnected-(JP2-Pad39)") (class "Default")
      (node (ref "JP2") (pin "39") (pinfunction "39_39") (pintype "passive"))
    )
    (net (code "90") (name "unconnected-(JP2-Pad40)") (class "Default")
      (node (ref "JP2") (pin "40") (pinfunction "40_40") (pintype "passive"))
    )
    (net (code "91") (name "unconnected-(MCP9808-VOUT-Pad3)") (class "Default")
      (node (ref "MCP9808") (pin "3") (pinfunction "VOUT_3") (pintype "bidirectional"))
    )
    (net (code "92") (name "unconnected-(U2-PA02(AIN0{slash}DAC)-Pad3)") (class "Default")
      (node (ref "U2") (pin "3") (pinfunction "PA02(AIN0/DAC)_3") (pintype "bidirectional"))
    )
    (net (code "93") (name "unconnected-(U2-PA03(AIN1{slash}REFA)-Pad4)") (class "Default")
      (node (ref "U2") (pin "4") (pinfunction "PA03(AIN1/REFA)_4") (pintype "bidirectional"))
    )
    (net (code "94") (name "unconnected-(U2-PA04(AIN4{slash}REFB{slash}SER0:0{slash}TC0:0)-Pad9)") (class "Default")
      (node (ref "U2") (pin "9") (pinfunction "PA04(AIN4/REFB/SER0:0/TC0:0)_9") (pintype "bidirectional"))
    )
    (net (code "95") (name "unconnected-(U2-PA08(I2C{slash}AIN16{slash}SER0:0+)-Pad13)") (class "Default")
      (node (ref "U2") (pin "13") (pinfunction "PA08(I2C/AIN16/SER0:0+)_13") (pintype "bidirectional"))
    )
    (net (code "96") (name "unconnected-(U2-PA09(I2C{slash}AIN17{slash}SER0:1+)-Pad14)") (class "Default")
      (node (ref "U2") (pin "14") (pinfunction "PA09(I2C/AIN17/SER0:1+)_14") (pintype "bidirectional"))
    )
    (net (code "97") (name "unconnected-(U2-PA12(I2C{slash}SER2:0+)-Pad21)") (class "Default")
      (node (ref "U2") (pin "21") (pinfunction "PA12(I2C/SER2:0+)_21") (pintype "bidirectional"))
    )
    (net (code "98") (name "unconnected-(U2-PA13(I2C{slash}SER2:1+)-Pad22)") (class "Default")
      (node (ref "U2") (pin "22") (pinfunction "PA13(I2C/SER2:1+)_22") (pintype "bidirectional"))
    )
    (net (code "99") (name "unconnected-(U2-PA14(XIN{slash}SER2:2+)-Pad23)") (class "Default")
      (node (ref "U2") (pin "23") (pinfunction "PA14(XIN/SER2:2+)_23") (pintype "bidirectional"))
    )
    (net (code "100") (name "unconnected-(U2-PA18(SER1:2+)-Pad27)") (class "Default")
      (node (ref "U2") (pin "27") (pinfunction "PA18(SER1:2+)_27") (pintype "bidirectional"))
    )
    (net (code "101") (name "unconnected-(U2-PA19(SER1:3+)-Pad28)") (class "Default")
      (node (ref "U2") (pin "28") (pinfunction "PA19(SER1:3+)_28") (pintype "bidirectional"))
    )
    (net (code "102") (name "unconnected-(U2-PA20(SER5:2+)-Pad29)") (class "Default")
      (node (ref "U2") (pin "29") (pinfunction "PA20(SER5:2+)_29") (pintype "bidirectional"))
    )
    (net (code "103") (name "unconnected-(U2-PA27-Pad39)") (class "Default")
      (node (ref "U2") (pin "39") (pinfunction "PA27_39") (pintype "bidirectional"))
    )
    (net (code "104") (name "unconnected-(U2-PA28-Pad41)") (class "Default")
      (node (ref "U2") (pin "41") (pinfunction "PA28_41") (pintype "bidirectional"))
    )
    (net (code "105") (name "unconnected-(U2-PB03(AIN11{slash}SER5:1)-Pad48)") (class "Default")
      (node (ref "U2") (pin "48") (pinfunction "PB03(AIN11/SER5:1)_48") (pintype "bidirectional"))
    )
    (net (code "106") (name "unconnected-(U2-PB08(AIN2{slash}SER4:0{slash}TC4:0)-Pad7)") (class "Default")
      (node (ref "U2") (pin "7") (pinfunction "PB08(AIN2/SER4:0/TC4:0)_7") (pintype "bidirectional"))
    )
    (net (code "107") (name "unconnected-(U2-PB09(AIN3{slash}SER4:1{slash}TC4:1)-Pad8)") (class "Default")
      (node (ref "U2") (pin "8") (pinfunction "PB09(AIN3/SER4:1/TC4:1)_8") (pintype "bidirectional"))
    )
    (net (code "108") (name "unconnected-(U2-PB10(SER4:2+)-Pad19)") (class "Default")
      (node (ref "U2") (pin "19") (pinfunction "PB10(SER4:2+)_19") (pintype "bidirectional"))
    )
    (net (code "109") (name "unconnected-(U2-PB11(SER4:3+)-Pad20)") (class "Default")
      (node (ref "U2") (pin "20") (pinfunction "PB11(SER4:3+)_20") (pintype "bidirectional"))
    )
    (net (code "110") (name "unconnected-(U2-PB22(SER5:2+)-Pad37)") (class "Default")
      (node (ref "U2") (pin "37") (pinfunction "PB22(SER5:2+)_37") (pintype "bidirectional"))
    )
    (net (code "111") (name "unconnected-(X2-Pad4)") (class "Default")
      (node (ref "X2") (pin "4") (pinfunction "4_4") (pintype "passive"))
    )
  )
)
